# SCH_For_IN12.net
KiCad netlist of a schematic drawn in Altium Designer
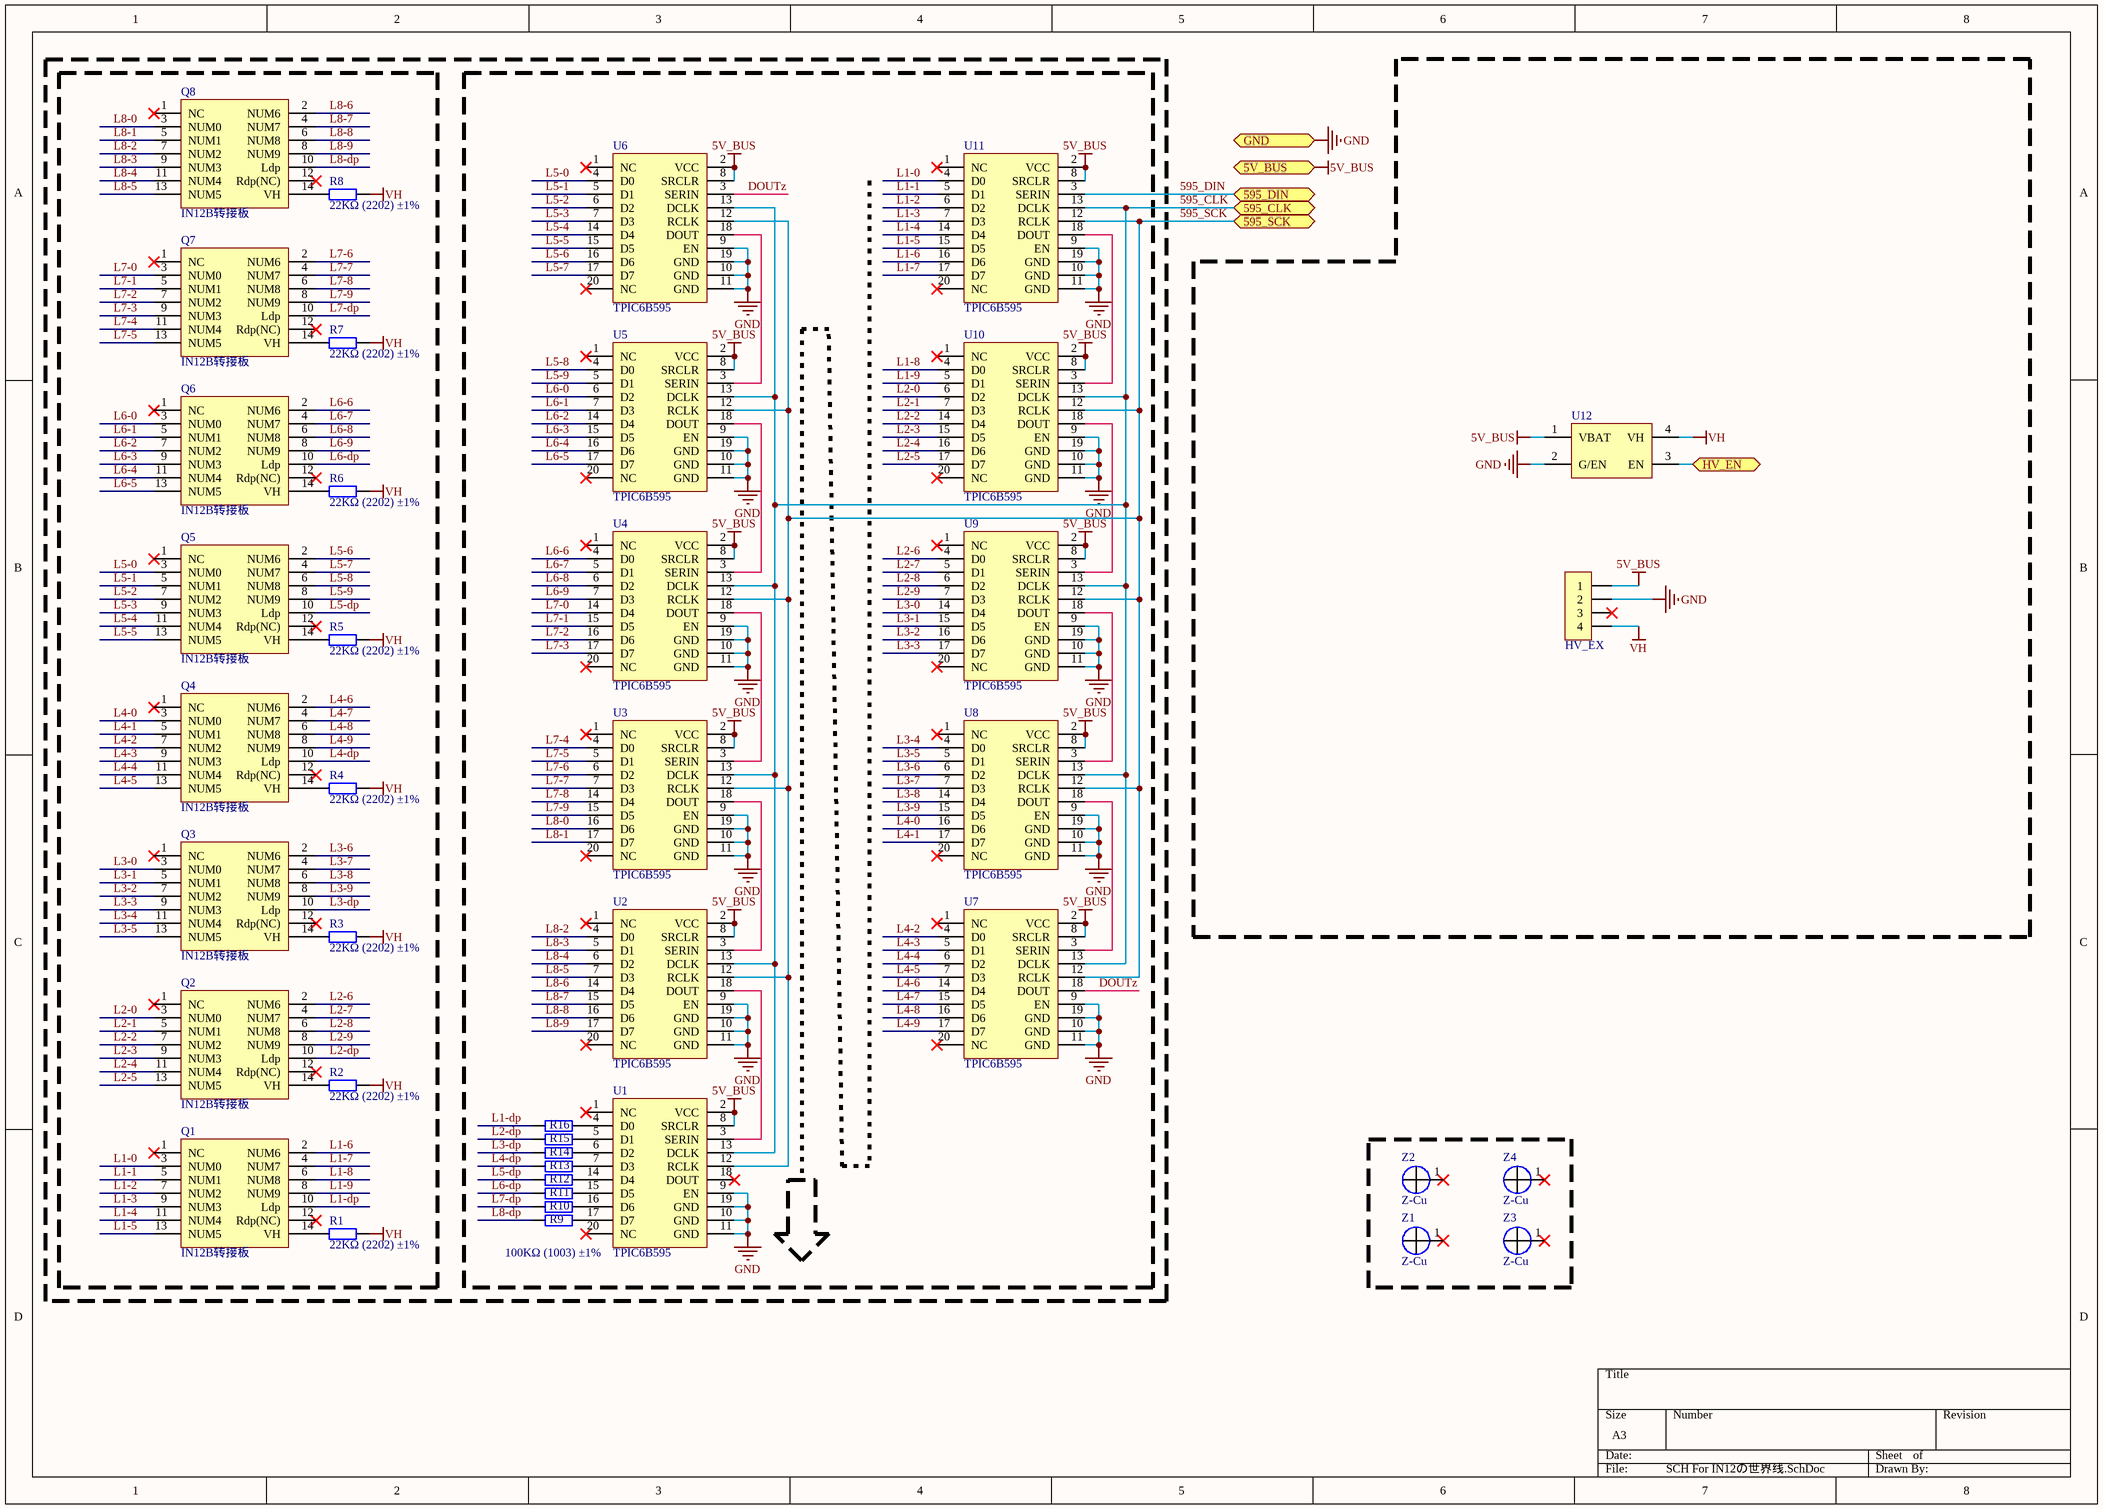
[diagram p0: SCH For IN12の世界线.SchDoc]

(export (version "E")
  (design (tool "Eeschema 10.0.6"))
  (components
    (comp (ref "HV_EX")
      (value "HDR-1X4")
      (footprint "HDR2.54-WS-4P")
      (description "4P接插件")
      (fields (field (name "版权归属") "源创客"))
      (libsource (lib "4.5   - 接插件-脚距2.54") (part "Header 4"))
    )
    (comp (ref "Q1")
      (value "IN12B转接板")
      (footprint "NIXIE IN12 Trans")
      (description "CCCP IN12B转接板")
      (fields (field (name "DESIGN BY：") "simonire@qq.com"))
      (libsource (lib "NIXIE TUBE") (part "NIXIE IN-12B转接板"))
    )
    (comp (ref "Q2")
      (value "IN12B转接板")
      (footprint "NIXIE IN12 Trans")
      (description "CCCP IN12B转接板")
      (fields (field (name "DESIGN BY：") "simonire@qq.com"))
      (libsource (lib "NIXIE TUBE") (part "NIXIE IN-12B转接板"))
    )
    (comp (ref "Q3")
      (value "IN12B转接板")
      (footprint "NIXIE IN12 Trans")
      (description "CCCP IN12B转接板")
      (fields (field (name "DESIGN BY：") "simonire@qq.com"))
      (libsource (lib "NIXIE TUBE") (part "NIXIE IN-12B转接板"))
    )
    (comp (ref "Q4")
      (value "IN12B转接板")
      (footprint "NIXIE IN12 Trans")
      (description "CCCP IN12B转接板")
      (fields (field (name "DESIGN BY：") "simonire@qq.com"))
      (libsource (lib "NIXIE TUBE") (part "NIXIE IN-12B转接板"))
    )
    (comp (ref "Q5")
      (value "IN12B转接板")
      (footprint "NIXIE IN12 Trans")
      (description "CCCP IN12B转接板")
      (fields (field (name "DESIGN BY：") "simonire@qq.com"))
      (libsource (lib "NIXIE TUBE") (part "NIXIE IN-12B转接板"))
    )
    (comp (ref "Q6")
      (value "IN12B转接板")
      (footprint "NIXIE IN12 Trans")
      (description "CCCP IN12B转接板")
      (fields (field (name "DESIGN BY：") "simonire@qq.com"))
      (libsource (lib "NIXIE TUBE") (part "NIXIE IN-12B转接板"))
    )
    (comp (ref "Q7")
      (value "IN12B转接板")
      (footprint "NIXIE IN12 Trans")
      (description "CCCP IN12B转接板")
      (fields (field (name "DESIGN BY：") "simonire@qq.com"))
      (libsource (lib "NIXIE TUBE") (part "NIXIE IN-12B转接板"))
    )
    (comp (ref "Q8")
      (value "IN12B转接板")
      (footprint "NIXIE IN12 Trans")
      (description "CCCP IN12B转接板")
      (fields (field (name "DESIGN BY：") "simonire@qq.com"))
      (libsource (lib "NIXIE TUBE") (part "NIXIE IN-12B转接板"))
    )
    (comp (ref "R1")
      (value "22KΩ (2202) ±1%")
      (footprint "LC-0805_R")
      (description "贴片电阻")
      (libsource (lib "Miscellaneous Devices LC") (part "0805 22KΩ (2202) 1%"))
    )
    (comp (ref "R2")
      (value "22KΩ (2202) ±1%")
      (footprint "LC-0805_R")
      (description "贴片电阻")
      (libsource (lib "Miscellaneous Devices LC") (part "0805 22KΩ (2202) 1%"))
    )
    (comp (ref "R3")
      (value "22KΩ (2202) ±1%")
      (footprint "LC-0805_R")
      (description "贴片电阻")
      (libsource (lib "Miscellaneous Devices LC") (part "0805 22KΩ (2202) 1%"))
    )
    (comp (ref "R4")
      (value "22KΩ (2202) ±1%")
      (footprint "LC-0805_R")
      (description "贴片电阻")
      (libsource (lib "Miscellaneous Devices LC") (part "0805 22KΩ (2202) 1%"))
    )
    (comp (ref "R5")
      (value "22KΩ (2202) ±1%")
      (footprint "LC-0805_R")
      (description "贴片电阻")
      (libsource (lib "Miscellaneous Devices LC") (part "0805 22KΩ (2202) 1%"))
    )
    (comp (ref "R6")
      (value "22KΩ (2202) ±1%")
      (footprint "LC-0805_R")
      (description "贴片电阻")
      (libsource (lib "Miscellaneous Devices LC") (part "0805 22KΩ (2202) 1%"))
    )
    (comp (ref "R7")
      (value "22KΩ (2202) ±1%")
      (footprint "LC-0805_R")
      (description "贴片电阻")
      (libsource (lib "Miscellaneous Devices LC") (part "0805 22KΩ (2202) 1%"))
    )
    (comp (ref "R8")
      (value "22KΩ (2202) ±1%")
      (footprint "LC-0805_R")
      (description "贴片电阻")
      (libsource (lib "Miscellaneous Devices LC") (part "0805 22KΩ (2202) 1%"))
    )
    (comp (ref "R9")
      (value "100KΩ (1003) ±1%")
      (footprint "LC-0603_R")
      (description "贴片电阻")
      (libsource (lib "Miscellaneous Devices LC") (part "0603 100KΩ (1003) 1%"))
    )
    (comp (ref "R10")
      (value "100KΩ (1003) ±1%")
      (footprint "LC-0603_R")
      (description "贴片电阻")
      (libsource (lib "Miscellaneous Devices LC") (part "0603 100KΩ (1003) 1%"))
    )
    (comp (ref "R11")
      (value "100KΩ (1003) ±1%")
      (footprint "LC-0603_R")
      (description "贴片电阻")
      (libsource (lib "Miscellaneous Devices LC") (part "0603 100KΩ (1003) 1%"))
    )
    (comp (ref "R12")
      (value "100KΩ (1003) ±1%")
      (footprint "LC-0603_R")
      (description "贴片电阻")
      (libsource (lib "Miscellaneous Devices LC") (part "0603 100KΩ (1003) 1%"))
    )
    (comp (ref "R13")
      (value "100KΩ (1003) ±1%")
      (footprint "LC-0603_R")
      (description "贴片电阻")
      (libsource (lib "Miscellaneous Devices LC") (part "0603 100KΩ (1003) 1%"))
    )
    (comp (ref "R14")
      (value "100KΩ (1003) ±1%")
      (footprint "LC-0603_R")
      (description "贴片电阻")
      (libsource (lib "Miscellaneous Devices LC") (part "0603 100KΩ (1003) 1%"))
    )
    (comp (ref "R15")
      (value "100KΩ (1003) ±1%")
      (footprint "LC-0603_R")
      (description "贴片电阻")
      (libsource (lib "Miscellaneous Devices LC") (part "0603 100KΩ (1003) 1%"))
    )
    (comp (ref "R16")
      (value "100KΩ (1003) ±1%")
      (footprint "LC-0603_R")
      (description "贴片电阻")
      (libsource (lib "Miscellaneous Devices LC") (part "0603 100KΩ (1003) 1%"))
    )
    (comp (ref "U1")
      (value "TPIC6B595")
      (footprint "SOIC_20W")
      (description "8bits译码驱动器")
      (libsource (lib "NIXIE TUBE") (part "TPIC6B595"))
    )
    (comp (ref "U2")
      (value "TPIC6B595")
      (footprint "SOIC_20W")
      (description "8bits译码驱动器")
      (libsource (lib "NIXIE TUBE") (part "TPIC6B595"))
    )
    (comp (ref "U3")
      (value "TPIC6B595")
      (footprint "SOIC_20W")
      (description "8bits译码驱动器")
      (libsource (lib "NIXIE TUBE") (part "TPIC6B595"))
    )
    (comp (ref "U4")
      (value "TPIC6B595")
      (footprint "SOIC_20W")
      (description "8bits译码驱动器")
      (libsource (lib "NIXIE TUBE") (part "TPIC6B595"))
    )
    (comp (ref "U5")
      (value "TPIC6B595")
      (footprint "SOIC_20W")
      (description "8bits译码驱动器")
      (libsource (lib "NIXIE TUBE") (part "TPIC6B595"))
    )
    (comp (ref "U6")
      (value "TPIC6B595")
      (footprint "SOIC_20W")
      (description "8bits译码驱动器")
      (libsource (lib "NIXIE TUBE") (part "TPIC6B595"))
    )
    (comp (ref "U7")
      (value "TPIC6B595")
      (footprint "SOIC_20W")
      (description "8bits译码驱动器")
      (libsource (lib "NIXIE TUBE") (part "TPIC6B595"))
    )
    (comp (ref "U8")
      (value "TPIC6B595")
      (footprint "SOIC_20W")
      (description "8bits译码驱动器")
      (libsource (lib "NIXIE TUBE") (part "TPIC6B595"))
    )
    (comp (ref "U9")
      (value "TPIC6B595")
      (footprint "SOIC_20W")
      (description "8bits译码驱动器")
      (libsource (lib "NIXIE TUBE") (part "TPIC6B595"))
    )
    (comp (ref "U10")
      (value "TPIC6B595")
      (footprint "SOIC_20W")
      (description "8bits译码驱动器")
      (libsource (lib "NIXIE TUBE") (part "TPIC6B595"))
    )
    (comp (ref "U11")
      (value "TPIC6B595")
      (footprint "SOIC_20W")
      (description "8bits译码驱动器")
      (libsource (lib "NIXIE TUBE") (part "TPIC6B595"))
    )
    (comp (ref "U12")
      (value "DCDC")
      (footprint "VH-DuDu")
      (description "5V升压驱动")
      (fields (field (name "DESIGN BY：") "simonire@qq.com"))
      (libsource (lib "NIXIE TUBE") (part "5V-{gt}VH"))
    )
    (comp (ref "Z1")
      (value "Z-Cu")
      (footprint "M3x5_L")
      (description "Cu")
      (libsource (lib "AD三维集成库") (part "Z-Cu"))
    )
    (comp (ref "Z2")
      (value "Z-Cu")
      (footprint "M3x5_L")
      (description "Cu")
      (libsource (lib "AD三维集成库") (part "Z-Cu"))
    )
    (comp (ref "Z3")
      (value "Z-Cu")
      (footprint "M3x5_L")
      (description "Cu")
      (libsource (lib "AD三维集成库") (part "Z-Cu"))
    )
    (comp (ref "Z4")
      (value "Z-Cu")
      (footprint "M3x5_L")
      (description "Cu")
      (libsource (lib "AD三维集成库") (part "Z-Cu"))
    )
  )
  (nets
    (net (code "1") (name "/595_CLK") (class "Default")
      (node (ref "U1") (pin "13") (pinfunction "DCLK_13") (pintype "passive"))
      (node (ref "U10") (pin "13") (pinfunction "DCLK_13") (pintype "passive"))
      (node (ref "U11") (pin "13") (pinfunction "DCLK_13") (pintype "passive"))
      (node (ref "U2") (pin "13") (pinfunction "DCLK_13") (pintype "passive"))
      (node (ref "U3") (pin "13") (pinfunction "DCLK_13") (pintype "passive"))
      (node (ref "U4") (pin "13") (pinfunction "DCLK_13") (pintype "passive"))
      (node (ref "U5") (pin "13") (pinfunction "DCLK_13") (pintype "passive"))
      (node (ref "U6") (pin "13") (pinfunction "DCLK_13") (pintype "passive"))
      (node (ref "U7") (pin "13") (pinfunction "DCLK_13") (pintype "passive"))
      (node (ref "U8") (pin "13") (pinfunction "DCLK_13") (pintype "passive"))
      (node (ref "U9") (pin "13") (pinfunction "DCLK_13") (pintype "passive"))
    )
    (net (code "2") (name "/595_DIN") (class "Default")
      (node (ref "U11") (pin "3") (pinfunction "SERIN_3") (pintype "passive"))
    )
    (net (code "3") (name "/595_SCK") (class "Default")
      (node (ref "U1") (pin "12") (pinfunction "RCLK_12") (pintype "passive"))
      (node (ref "U10") (pin "12") (pinfunction "RCLK_12") (pintype "passive"))
      (node (ref "U11") (pin "12") (pinfunction "RCLK_12") (pintype "passive"))
      (node (ref "U2") (pin "12") (pinfunction "RCLK_12") (pintype "passive"))
      (node (ref "U3") (pin "12") (pinfunction "RCLK_12") (pintype "passive"))
      (node (ref "U4") (pin "12") (pinfunction "RCLK_12") (pintype "passive"))
      (node (ref "U5") (pin "12") (pinfunction "RCLK_12") (pintype "passive"))
      (node (ref "U6") (pin "12") (pinfunction "RCLK_12") (pintype "passive"))
      (node (ref "U7") (pin "12") (pinfunction "RCLK_12") (pintype "passive"))
      (node (ref "U8") (pin "12") (pinfunction "RCLK_12") (pintype "passive"))
      (node (ref "U9") (pin "12") (pinfunction "RCLK_12") (pintype "passive"))
    )
    (net (code "4") (name "/DOUTz") (class "Default")
      (node (ref "U6") (pin "3") (pinfunction "SERIN_3") (pintype "passive"))
      (node (ref "U7") (pin "18") (pinfunction "DOUT_18") (pintype "passive"))
    )
    (net (code "5") (name "/HV_EN") (class "Default")
      (node (ref "U12") (pin "3") (pinfunction "EN_3") (pintype "passive"))
    )
    (net (code "6") (name "/L1-0") (class "Default")
      (node (ref "Q1") (pin "3") (pinfunction "NUM0_3") (pintype "passive"))
      (node (ref "U11") (pin "4") (pinfunction "D0_4") (pintype "passive"))
    )
    (net (code "7") (name "/L1-1") (class "Default")
      (node (ref "Q1") (pin "5") (pinfunction "NUM1_5") (pintype "passive"))
      (node (ref "U11") (pin "5") (pinfunction "D1_5") (pintype "passive"))
    )
    (net (code "8") (name "/L1-2") (class "Default")
      (node (ref "Q1") (pin "7") (pinfunction "NUM2_7") (pintype "passive"))
      (node (ref "U11") (pin "6") (pinfunction "D2_6") (pintype "passive"))
    )
    (net (code "9") (name "/L1-3") (class "Default")
      (node (ref "Q1") (pin "9") (pinfunction "NUM3_9") (pintype "passive"))
      (node (ref "U11") (pin "7") (pinfunction "D3_7") (pintype "passive"))
    )
    (net (code "10") (name "/L1-4") (class "Default")
      (node (ref "Q1") (pin "11") (pinfunction "NUM4_11") (pintype "passive"))
      (node (ref "U11") (pin "14") (pinfunction "D4_14") (pintype "passive"))
    )
    (net (code "11") (name "/L1-5") (class "Default")
      (node (ref "Q1") (pin "13") (pinfunction "NUM5_13") (pintype "passive"))
      (node (ref "U11") (pin "15") (pinfunction "D5_15") (pintype "passive"))
    )
    (net (code "12") (name "/L1-6") (class "Default")
      (node (ref "Q1") (pin "2") (pinfunction "NUM6_2") (pintype "passive"))
      (node (ref "U11") (pin "16") (pinfunction "D6_16") (pintype "passive"))
    )
    (net (code "13") (name "/L1-7") (class "Default")
      (node (ref "Q1") (pin "4") (pinfunction "NUM7_4") (pintype "passive"))
      (node (ref "U11") (pin "17") (pinfunction "D7_17") (pintype "passive"))
    )
    (net (code "14") (name "/L1-8") (class "Default")
      (node (ref "Q1") (pin "6") (pinfunction "NUM8_6") (pintype "passive"))
      (node (ref "U10") (pin "4") (pinfunction "D0_4") (pintype "passive"))
    )
    (net (code "15") (name "/L1-9") (class "Default")
      (node (ref "Q1") (pin "8") (pinfunction "NUM9_8") (pintype "passive"))
      (node (ref "U10") (pin "5") (pinfunction "D1_5") (pintype "passive"))
    )
    (net (code "16") (name "/L1-dp") (class "Default")
      (node (ref "Q1") (pin "10") (pinfunction "Ldp_10") (pintype "passive"))
      (node (ref "R16") (pin "1") (pinfunction "1_1") (pintype "passive"))
    )
    (net (code "17") (name "/L2-0") (class "Default")
      (node (ref "Q2") (pin "3") (pinfunction "NUM0_3") (pintype "passive"))
      (node (ref "U10") (pin "6") (pinfunction "D2_6") (pintype "passive"))
    )
    (net (code "18") (name "/L2-1") (class "Default")
      (node (ref "Q2") (pin "5") (pinfunction "NUM1_5") (pintype "passive"))
      (node (ref "U10") (pin "7") (pinfunction "D3_7") (pintype "passive"))
    )
    (net (code "19") (name "/L2-2") (class "Default")
      (node (ref "Q2") (pin "7") (pinfunction "NUM2_7") (pintype "passive"))
      (node (ref "U10") (pin "14") (pinfunction "D4_14") (pintype "passive"))
    )
    (net (code "20") (name "/L2-3") (class "Default")
      (node (ref "Q2") (pin "9") (pinfunction "NUM3_9") (pintype "passive"))
      (node (ref "U10") (pin "15") (pinfunction "D5_15") (pintype "passive"))
    )
    (net (code "21") (name "/L2-4") (class "Default")
      (node (ref "Q2") (pin "11") (pinfunction "NUM4_11") (pintype "passive"))
      (node (ref "U10") (pin "16") (pinfunction "D6_16") (pintype "passive"))
    )
    (net (code "22") (name "/L2-5") (class "Default")
      (node (ref "Q2") (pin "13") (pinfunction "NUM5_13") (pintype "passive"))
      (node (ref "U10") (pin "17") (pinfunction "D7_17") (pintype "passive"))
    )
    (net (code "23") (name "/L2-6") (class "Default")
      (node (ref "Q2") (pin "2") (pinfunction "NUM6_2") (pintype "passive"))
      (node (ref "U9") (pin "4") (pinfunction "D0_4") (pintype "passive"))
    )
    (net (code "24") (name "/L2-7") (class "Default")
      (node (ref "Q2") (pin "4") (pinfunction "NUM7_4") (pintype "passive"))
      (node (ref "U9") (pin "5") (pinfunction "D1_5") (pintype "passive"))
    )
    (net (code "25") (name "/L2-8") (class "Default")
      (node (ref "Q2") (pin "6") (pinfunction "NUM8_6") (pintype "passive"))
      (node (ref "U9") (pin "6") (pinfunction "D2_6") (pintype "passive"))
    )
    (net (code "26") (name "/L2-9") (class "Default")
      (node (ref "Q2") (pin "8") (pinfunction "NUM9_8") (pintype "passive"))
      (node (ref "U9") (pin "7") (pinfunction "D3_7") (pintype "passive"))
    )
    (net (code "27") (name "/L2-dp") (class "Default")
      (node (ref "Q2") (pin "10") (pinfunction "Ldp_10") (pintype "passive"))
      (node (ref "R15") (pin "1") (pinfunction "1_1") (pintype "passive"))
    )
    (net (code "28") (name "/L3-0") (class "Default")
      (node (ref "Q3") (pin "3") (pinfunction "NUM0_3") (pintype "passive"))
      (node (ref "U9") (pin "14") (pinfunction "D4_14") (pintype "passive"))
    )
    (net (code "29") (name "/L3-1") (class "Default")
      (node (ref "Q3") (pin "5") (pinfunction "NUM1_5") (pintype "passive"))
      (node (ref "U9") (pin "15") (pinfunction "D5_15") (pintype "passive"))
    )
    (net (code "30") (name "/L3-2") (class "Default")
      (node (ref "Q3") (pin "7") (pinfunction "NUM2_7") (pintype "passive"))
      (node (ref "U9") (pin "16") (pinfunction "D6_16") (pintype "passive"))
    )
    (net (code "31") (name "/L3-3") (class "Default")
      (node (ref "Q3") (pin "9") (pinfunction "NUM3_9") (pintype "passive"))
      (node (ref "U9") (pin "17") (pinfunction "D7_17") (pintype "passive"))
    )
    (net (code "32") (name "/L3-4") (class "Default")
      (node (ref "Q3") (pin "11") (pinfunction "NUM4_11") (pintype "passive"))
      (node (ref "U8") (pin "4") (pinfunction "D0_4") (pintype "passive"))
    )
    (net (code "33") (name "/L3-5") (class "Default")
      (node (ref "Q3") (pin "13") (pinfunction "NUM5_13") (pintype "passive"))
      (node (ref "U8") (pin "5") (pinfunction "D1_5") (pintype "passive"))
    )
    (net (code "34") (name "/L3-6") (class "Default")
      (node (ref "Q3") (pin "2") (pinfunction "NUM6_2") (pintype "passive"))
      (node (ref "U8") (pin "6") (pinfunction "D2_6") (pintype "passive"))
    )
    (net (code "35") (name "/L3-7") (class "Default")
      (node (ref "Q3") (pin "4") (pinfunction "NUM7_4") (pintype "passive"))
      (node (ref "U8") (pin "7") (pinfunction "D3_7") (pintype "passive"))
    )
    (net (code "36") (name "/L3-8") (class "Default")
      (node (ref "Q3") (pin "6") (pinfunction "NUM8_6") (pintype "passive"))
      (node (ref "U8") (pin "14") (pinfunction "D4_14") (pintype "passive"))
    )
    (net (code "37") (name "/L3-9") (class "Default")
      (node (ref "Q3") (pin "8") (pinfunction "NUM9_8") (pintype "passive"))
      (node (ref "U8") (pin "15") (pinfunction "D5_15") (pintype "passive"))
    )
    (net (code "38") (name "/L3-dp") (class "Default")
      (node (ref "Q3") (pin "10") (pinfunction "Ldp_10") (pintype "passive"))
      (node (ref "R14") (pin "1") (pinfunction "1_1") (pintype "passive"))
    )
    (net (code "39") (name "/L4-0") (class "Default")
      (node (ref "Q4") (pin "3") (pinfunction "NUM0_3") (pintype "passive"))
      (node (ref "U8") (pin "16") (pinfunction "D6_16") (pintype "passive"))
    )
    (net (code "40") (name "/L4-1") (class "Default")
      (node (ref "Q4") (pin "5") (pinfunction "NUM1_5") (pintype "passive"))
      (node (ref "U8") (pin "17") (pinfunction "D7_17") (pintype "passive"))
    )
    (net (code "41") (name "/L4-2") (class "Default")
      (node (ref "Q4") (pin "7") (pinfunction "NUM2_7") (pintype "passive"))
      (node (ref "U7") (pin "4") (pinfunction "D0_4") (pintype "passive"))
    )
    (net (code "42") (name "/L4-3") (class "Default")
      (node (ref "Q4") (pin "9") (pinfunction "NUM3_9") (pintype "passive"))
      (node (ref "U7") (pin "5") (pinfunction "D1_5") (pintype "passive"))
    )
    (net (code "43") (name "/L4-4") (class "Default")
      (node (ref "Q4") (pin "11") (pinfunction "NUM4_11") (pintype "passive"))
      (node (ref "U7") (pin "6") (pinfunction "D2_6") (pintype "passive"))
    )
    (net (code "44") (name "/L4-5") (class "Default")
      (node (ref "Q4") (pin "13") (pinfunction "NUM5_13") (pintype "passive"))
      (node (ref "U7") (pin "7") (pinfunction "D3_7") (pintype "passive"))
    )
    (net (code "45") (name "/L4-6") (class "Default")
      (node (ref "Q4") (pin "2") (pinfunction "NUM6_2") (pintype "passive"))
      (node (ref "U7") (pin "14") (pinfunction "D4_14") (pintype "passive"))
    )
    (net (code "46") (name "/L4-7") (class "Default")
      (node (ref "Q4") (pin "4") (pinfunction "NUM7_4") (pintype "passive"))
      (node (ref "U7") (pin "15") (pinfunction "D5_15") (pintype "passive"))
    )
    (net (code "47") (name "/L4-8") (class "Default")
      (node (ref "Q4") (pin "6") (pinfunction "NUM8_6") (pintype "passive"))
      (node (ref "U7") (pin "16") (pinfunction "D6_16") (pintype "passive"))
    )
    (net (code "48") (name "/L4-9") (class "Default")
      (node (ref "Q4") (pin "8") (pinfunction "NUM9_8") (pintype "passive"))
      (node (ref "U7") (pin "17") (pinfunction "D7_17") (pintype "passive"))
    )
    (net (code "49") (name "/L4-dp") (class "Default")
      (node (ref "Q4") (pin "10") (pinfunction "Ldp_10") (pintype "passive"))
      (node (ref "R13") (pin "1") (pinfunction "1_1") (pintype "passive"))
    )
    (net (code "50") (name "/L5-0") (class "Default")
      (node (ref "Q5") (pin "3") (pinfunction "NUM0_3") (pintype "passive"))
      (node (ref "U6") (pin "4") (pinfunction "D0_4") (pintype "passive"))
    )
    (net (code "51") (name "/L5-1") (class "Default")
      (node (ref "Q5") (pin "5") (pinfunction "NUM1_5") (pintype "passive"))
      (node (ref "U6") (pin "5") (pinfunction "D1_5") (pintype "passive"))
    )
    (net (code "52") (name "/L5-2") (class "Default")
      (node (ref "Q5") (pin "7") (pinfunction "NUM2_7") (pintype "passive"))
      (node (ref "U6") (pin "6") (pinfunction "D2_6") (pintype "passive"))
    )
    (net (code "53") (name "/L5-3") (class "Default")
      (node (ref "Q5") (pin "9") (pinfunction "NUM3_9") (pintype "passive"))
      (node (ref "U6") (pin "7") (pinfunction "D3_7") (pintype "passive"))
    )
    (net (code "54") (name "/L5-4") (class "Default")
      (node (ref "Q5") (pin "11") (pinfunction "NUM4_11") (pintype "passive"))
      (node (ref "U6") (pin "14") (pinfunction "D4_14") (pintype "passive"))
    )
    (net (code "55") (name "/L5-5") (class "Default")
      (node (ref "Q5") (pin "13") (pinfunction "NUM5_13") (pintype "passive"))
      (node (ref "U6") (pin "15") (pinfunction "D5_15") (pintype "passive"))
    )
    (net (code "56") (name "/L5-6") (class "Default")
      (node (ref "Q5") (pin "2") (pinfunction "NUM6_2") (pintype "passive"))
      (node (ref "U6") (pin "16") (pinfunction "D6_16") (pintype "passive"))
    )
    (net (code "57") (name "/L5-7") (class "Default")
      (node (ref "Q5") (pin "4") (pinfunction "NUM7_4") (pintype "passive"))
      (node (ref "U6") (pin "17") (pinfunction "D7_17") (pintype "passive"))
    )
    (net (code "58") (name "/L5-8") (class "Default")
      (node (ref "Q5") (pin "6") (pinfunction "NUM8_6") (pintype "passive"))
      (node (ref "U5") (pin "4") (pinfunction "D0_4") (pintype "passive"))
    )
    (net (code "59") (name "/L5-9") (class "Default")
      (node (ref "Q5") (pin "8") (pinfunction "NUM9_8") (pintype "passive"))
      (node (ref "U5") (pin "5") (pinfunction "D1_5") (pintype "passive"))
    )
    (net (code "60") (name "/L5-dp") (class "Default")
      (node (ref "Q5") (pin "10") (pinfunction "Ldp_10") (pintype "passive"))
      (node (ref "R12") (pin "1") (pinfunction "1_1") (pintype "passive"))
    )
    (net (code "61") (name "/L6-0") (class "Default")
      (node (ref "Q6") (pin "3") (pinfunction "NUM0_3") (pintype "passive"))
      (node (ref "U5") (pin "6") (pinfunction "D2_6") (pintype "passive"))
    )
    (net (code "62") (name "/L6-1") (class "Default")
      (node (ref "Q6") (pin "5") (pinfunction "NUM1_5") (pintype "passive"))
      (node (ref "U5") (pin "7") (pinfunction "D3_7") (pintype "passive"))
    )
    (net (code "63") (name "/L6-2") (class "Default")
      (node (ref "Q6") (pin "7") (pinfunction "NUM2_7") (pintype "passive"))
      (node (ref "U5") (pin "14") (pinfunction "D4_14") (pintype "passive"))
    )
    (net (code "64") (name "/L6-3") (class "Default")
      (node (ref "Q6") (pin "9") (pinfunction "NUM3_9") (pintype "passive"))
      (node (ref "U5") (pin "15") (pinfunction "D5_15") (pintype "passive"))
    )
    (net (code "65") (name "/L6-4") (class "Default")
      (node (ref "Q6") (pin "11") (pinfunction "NUM4_11") (pintype "passive"))
      (node (ref "U5") (pin "16") (pinfunction "D6_16") (pintype "passive"))
    )
    (net (code "66") (name "/L6-5") (class "Default")
      (node (ref "Q6") (pin "13") (pinfunction "NUM5_13") (pintype "passive"))
      (node (ref "U5") (pin "17") (pinfunction "D7_17") (pintype "passive"))
    )
    (net (code "67") (name "/L6-6") (class "Default")
      (node (ref "Q6") (pin "2") (pinfunction "NUM6_2") (pintype "passive"))
      (node (ref "U4") (pin "4") (pinfunction "D0_4") (pintype "passive"))
    )
    (net (code "68") (name "/L6-7") (class "Default")
      (node (ref "Q6") (pin "4") (pinfunction "NUM7_4") (pintype "passive"))
      (node (ref "U4") (pin "5") (pinfunction "D1_5") (pintype "passive"))
    )
    (net (code "69") (name "/L6-8") (class "Default")
      (node (ref "Q6") (pin "6") (pinfunction "NUM8_6") (pintype "passive"))
      (node (ref "U4") (pin "6") (pinfunction "D2_6") (pintype "passive"))
    )
    (net (code "70") (name "/L6-9") (class "Default")
      (node (ref "Q6") (pin "8") (pinfunction "NUM9_8") (pintype "passive"))
      (node (ref "U4") (pin "7") (pinfunction "D3_7") (pintype "passive"))
    )
    (net (code "71") (name "/L6-dp") (class "Default")
      (node (ref "Q6") (pin "10") (pinfunction "Ldp_10") (pintype "passive"))
      (node (ref "R11") (pin "1") (pinfunction "1_1") (pintype "passive"))
    )
    (net (code "72") (name "/L7-0") (class "Default")
      (node (ref "Q7") (pin "3") (pinfunction "NUM0_3") (pintype "passive"))
      (node (ref "U4") (pin "14") (pinfunction "D4_14") (pintype "passive"))
    )
    (net (code "73") (name "/L7-1") (class "Default")
      (node (ref "Q7") (pin "5") (pinfunction "NUM1_5") (pintype "passive"))
      (node (ref "U4") (pin "15") (pinfunction "D5_15") (pintype "passive"))
    )
    (net (code "74") (name "/L7-2") (class "Default")
      (node (ref "Q7") (pin "7") (pinfunction "NUM2_7") (pintype "passive"))
      (node (ref "U4") (pin "16") (pinfunction "D6_16") (pintype "passive"))
    )
    (net (code "75") (name "/L7-3") (class "Default")
      (node (ref "Q7") (pin "9") (pinfunction "NUM3_9") (pintype "passive"))
      (node (ref "U4") (pin "17") (pinfunction "D7_17") (pintype "passive"))
    )
    (net (code "76") (name "/L7-4") (class "Default")
      (node (ref "Q7") (pin "11") (pinfunction "NUM4_11") (pintype "passive"))
      (node (ref "U3") (pin "4") (pinfunction "D0_4") (pintype "passive"))
    )
    (net (code "77") (name "/L7-5") (class "Default")
      (node (ref "Q7") (pin "13") (pinfunction "NUM5_13") (pintype "passive"))
      (node (ref "U3") (pin "5") (pinfunction "D1_5") (pintype "passive"))
    )
    (net (code "78") (name "/L7-6") (class "Default")
      (node (ref "Q7") (pin "2") (pinfunction "NUM6_2") (pintype "passive"))
      (node (ref "U3") (pin "6") (pinfunction "D2_6") (pintype "passive"))
    )
    (net (code "79") (name "/L7-7") (class "Default")
      (node (ref "Q7") (pin "4") (pinfunction "NUM7_4") (pintype "passive"))
      (node (ref "U3") (pin "7") (pinfunction "D3_7") (pintype "passive"))
    )
    (net (code "80") (name "/L7-8") (class "Default")
      (node (ref "Q7") (pin "6") (pinfunction "NUM8_6") (pintype "passive"))
      (node (ref "U3") (pin "14") (pinfunction "D4_14") (pintype "passive"))
    )
    (net (code "81") (name "/L7-9") (class "Default")
      (node (ref "Q7") (pin "8") (pinfunction "NUM9_8") (pintype "passive"))
      (node (ref "U3") (pin "15") (pinfunction "D5_15") (pintype "passive"))
    )
    (net (code "82") (name "/L7-dp") (class "Default")
      (node (ref "Q7") (pin "10") (pinfunction "Ldp_10") (pintype "passive"))
      (node (ref "R10") (pin "1") (pinfunction "1_1") (pintype "passive"))
    )
    (net (code "83") (name "/L8-0") (class "Default")
      (node (ref "Q8") (pin "3") (pinfunction "NUM0_3") (pintype "passive"))
      (node (ref "U3") (pin "16") (pinfunction "D6_16") (pintype "passive"))
    )
    (net (code "84") (name "/L8-1") (class "Default")
      (node (ref "Q8") (pin "5") (pinfunction "NUM1_5") (pintype "passive"))
      (node (ref "U3") (pin "17") (pinfunction "D7_17") (pintype "passive"))
    )
    (net (code "85") (name "/L8-2") (class "Default")
      (node (ref "Q8") (pin "7") (pinfunction "NUM2_7") (pintype "passive"))
      (node (ref "U2") (pin "4") (pinfunction "D0_4") (pintype "passive"))
    )
    (net (code "86") (name "/L8-3") (class "Default")
      (node (ref "Q8") (pin "9") (pinfunction "NUM3_9") (pintype "passive"))
      (node (ref "U2") (pin "5") (pinfunction "D1_5") (pintype "passive"))
    )
    (net (code "87") (name "/L8-4") (class "Default")
      (node (ref "Q8") (pin "11") (pinfunction "NUM4_11") (pintype "passive"))
      (node (ref "U2") (pin "6") (pinfunction "D2_6") (pintype "passive"))
    )
    (net (code "88") (name "/L8-5") (class "Default")
      (node (ref "Q8") (pin "13") (pinfunction "NUM5_13") (pintype "passive"))
      (node (ref "U2") (pin "7") (pinfunction "D3_7") (pintype "passive"))
    )
    (net (code "89") (name "/L8-6") (class "Default")
      (node (ref "Q8") (pin "2") (pinfunction "NUM6_2") (pintype "passive"))
      (node (ref "U2") (pin "14") (pinfunction "D4_14") (pintype "passive"))
    )
    (net (code "90") (name "/L8-7") (class "Default")
      (node (ref "Q8") (pin "4") (pinfunction "NUM7_4") (pintype "passive"))
      (node (ref "U2") (pin "15") (pinfunction "D5_15") (pintype "passive"))
    )
    (net (code "91") (name "/L8-8") (class "Default")
      (node (ref "Q8") (pin "6") (pinfunction "NUM8_6") (pintype "passive"))
      (node (ref "U2") (pin "16") (pinfunction "D6_16") (pintype "passive"))
    )
    (net (code "92") (name "/L8-9") (class "Default")
      (node (ref "Q8") (pin "8") (pinfunction "NUM9_8") (pintype "passive"))
      (node (ref "U2") (pin "17") (pinfunction "D7_17") (pintype "passive"))
    )
    (net (code "93") (name "/L8-dp") (class "Default")
      (node (ref "Q8") (pin "10") (pinfunction "Ldp_10") (pintype "passive"))
      (node (ref "R9") (pin "1") (pinfunction "1_1") (pintype "passive"))
    )
    (net (code "94") (name "5V_BUS") (class "Default")
      (node (ref "HV_EX") (pin "1") (pinfunction "1_1") (pintype "passive"))
      (node (ref "U1") (pin "2") (pinfunction "VCC_2") (pintype "passive"))
      (node (ref "U1") (pin "8") (pinfunction "SRCLR_8") (pintype "passive"))
      (node (ref "U10") (pin "2") (pinfunction "VCC_2") (pintype "passive"))
      (node (ref "U10") (pin "8") (pinfunction "SRCLR_8") (pintype "passive"))
      (node (ref "U11") (pin "2") (pinfunction "VCC_2") (pintype "passive"))
      (node (ref "U11") (pin "8") (pinfunction "SRCLR_8") (pintype "passive"))
      (node (ref "U12") (pin "1") (pinfunction "VBAT_1") (pintype "passive"))
      (node (ref "U2") (pin "2") (pinfunction "VCC_2") (pintype "passive"))
      (node (ref "U2") (pin "8") (pinfunction "SRCLR_8") (pintype "passive"))
      (node (ref "U3") (pin "2") (pinfunction "VCC_2") (pintype "passive"))
      (node (ref "U3") (pin "8") (pinfunction "SRCLR_8") (pintype "passive"))
      (node (ref "U4") (pin "2") (pinfunction "VCC_2") (pintype "passive"))
      (node (ref "U4") (pin "8") (pinfunction "SRCLR_8") (pintype "passive"))
      (node (ref "U5") (pin "2") (pinfunction "VCC_2") (pintype "passive"))
      (node (ref "U5") (pin "8") (pinfunction "SRCLR_8") (pintype "passive"))
      (node (ref "U6") (pin "2") (pinfunction "VCC_2") (pintype "passive"))
      (node (ref "U6") (pin "8") (pinfunction "SRCLR_8") (pintype "passive"))
      (node (ref "U7") (pin "2") (pinfunction "VCC_2") (pintype "passive"))
      (node (ref "U7") (pin "8") (pinfunction "SRCLR_8") (pintype "passive"))
      (node (ref "U8") (pin "2") (pinfunction "VCC_2") (pintype "passive"))
      (node (ref "U8") (pin "8") (pinfunction "SRCLR_8") (pintype "passive"))
      (node (ref "U9") (pin "2") (pinfunction "VCC_2") (pintype "passive"))
      (node (ref "U9") (pin "8") (pinfunction "SRCLR_8") (pintype "passive"))
    )
    (net (code "95") (name "GND") (class "Default")
      (node (ref "HV_EX") (pin "2") (pinfunction "2_2") (pintype "passive"))
      (node (ref "U1") (pin "10") (pinfunction "GND_10") (pintype "passive"))
      (node (ref "U1") (pin "11") (pinfunction "GND_11") (pintype "passive"))
      (node (ref "U1") (pin "19") (pinfunction "GND_19") (pintype "passive"))
      (node (ref "U1") (pin "9") (pinfunction "EN_9") (pintype "passive"))
      (node (ref "U10") (pin "10") (pinfunction "GND_10") (pintype "passive"))
      (node (ref "U10") (pin "11") (pinfunction "GND_11") (pintype "passive"))
      (node (ref "U10") (pin "19") (pinfunction "GND_19") (pintype "passive"))
      (node (ref "U10") (pin "9") (pinfunction "EN_9") (pintype "passive"))
      (node (ref "U11") (pin "10") (pinfunction "GND_10") (pintype "passive"))
      (node (ref "U11") (pin "11") (pinfunction "GND_11") (pintype "passive"))
      (node (ref "U11") (pin "19") (pinfunction "GND_19") (pintype "passive"))
      (node (ref "U11") (pin "9") (pinfunction "EN_9") (pintype "passive"))
      (node (ref "U12") (pin "2") (pinfunction "G/EN_2") (pintype "passive"))
      (node (ref "U2") (pin "10") (pinfunction "GND_10") (pintype "passive"))
      (node (ref "U2") (pin "11") (pinfunction "GND_11") (pintype "passive"))
      (node (ref "U2") (pin "19") (pinfunction "GND_19") (pintype "passive"))
      (node (ref "U2") (pin "9") (pinfunction "EN_9") (pintype "passive"))
      (node (ref "U3") (pin "10") (pinfunction "GND_10") (pintype "passive"))
      (node (ref "U3") (pin "11") (pinfunction "GND_11") (pintype "passive"))
      (node (ref "U3") (pin "19") (pinfunction "GND_19") (pintype "passive"))
      (node (ref "U3") (pin "9") (pinfunction "EN_9") (pintype "passive"))
      (node (ref "U4") (pin "10") (pinfunction "GND_10") (pintype "passive"))
      (node (ref "U4") (pin "11") (pinfunction "GND_11") (pintype "passive"))
      (node (ref "U4") (pin "19") (pinfunction "GND_19") (pintype "passive"))
      (node (ref "U4") (pin "9") (pinfunction "EN_9") (pintype "passive"))
      (node (ref "U5") (pin "10") (pinfunction "GND_10") (pintype "passive"))
      (node (ref "U5") (pin "11") (pinfunction "GND_11") (pintype "passive"))
      (node (ref "U5") (pin "19") (pinfunction "GND_19") (pintype "passive"))
      (node (ref "U5") (pin "9") (pinfunction "EN_9") (pintype "passive"))
      (node (ref "U6") (pin "10") (pinfunction "GND_10") (pintype "passive"))
      (node (ref "U6") (pin "11") (pinfunction "GND_11") (pintype "passive"))
      (node (ref "U6") (pin "19") (pinfunction "GND_19") (pintype "passive"))
      (node (ref "U6") (pin "9") (pinfunction "EN_9") (pintype "passive"))
      (node (ref "U7") (pin "10") (pinfunction "GND_10") (pintype "passive"))
      (node (ref "U7") (pin "11") (pinfunction "GND_11") (pintype "passive"))
      (node (ref "U7") (pin "19") (pinfunction "GND_19") (pintype "passive"))
      (node (ref "U7") (pin "9") (pinfunction "EN_9") (pintype "passive"))
      (node (ref "U8") (pin "10") (pinfunction "GND_10") (pintype "passive"))
      (node (ref "U8") (pin "11") (pinfunction "GND_11") (pintype "passive"))
      (node (ref "U8") (pin "19") (pinfunction "GND_19") (pintype "passive"))
      (node (ref "U8") (pin "9") (pinfunction "EN_9") (pintype "passive"))
      (node (ref "U9") (pin "10") (pinfunction "GND_10") (pintype "passive"))
      (node (ref "U9") (pin "11") (pinfunction "GND_11") (pintype "passive"))
      (node (ref "U9") (pin "19") (pinfunction "GND_19") (pintype "passive"))
      (node (ref "U9") (pin "9") (pinfunction "EN_9") (pintype "passive"))
    )
    (net (code "96") (name "Net-(Q1-VH)") (class "Default")
      (node (ref "Q1") (pin "14") (pinfunction "VH_14") (pintype "passive"))
      (node (ref "R1") (pin "1") (pinfunction "1_1") (pintype "passive"))
    )
    (net (code "97") (name "Net-(Q2-VH)") (class "Default")
      (node (ref "Q2") (pin "14") (pinfunction "VH_14") (pintype "passive"))
      (node (ref "R2") (pin "1") (pinfunction "1_1") (pintype "passive"))
    )
    (net (code "98") (name "Net-(Q3-VH)") (class "Default")
      (node (ref "Q3") (pin "14") (pinfunction "VH_14") (pintype "passive"))
      (node (ref "R3") (pin "1") (pinfunction "1_1") (pintype "passive"))
    )
    (net (code "99") (name "Net-(Q4-VH)") (class "Default")
      (node (ref "Q4") (pin "14") (pinfunction "VH_14") (pintype "passive"))
      (node (ref "R4") (pin "1") (pinfunction "1_1") (pintype "passive"))
    )
    (net (code "100") (name "Net-(Q5-VH)") (class "Default")
      (node (ref "Q5") (pin "14") (pinfunction "VH_14") (pintype "passive"))
      (node (ref "R5") (pin "1") (pinfunction "1_1") (pintype "passive"))
    )
    (net (code "101") (name "Net-(Q6-VH)") (class "Default")
      (node (ref "Q6") (pin "14") (pinfunction "VH_14") (pintype "passive"))
      (node (ref "R6") (pin "1") (pinfunction "1_1") (pintype "passive"))
    )
    (net (code "102") (name "Net-(Q7-VH)") (class "Default")
      (node (ref "Q7") (pin "14") (pinfunction "VH_14") (pintype "passive"))
      (node (ref "R7") (pin "1") (pinfunction "1_1") (pintype "passive"))
    )
    (net (code "103") (name "Net-(Q8-VH)") (class "Default")
      (node (ref "Q8") (pin "14") (pinfunction "VH_14") (pintype "passive"))
      (node (ref "R8") (pin "1") (pinfunction "1_1") (pintype "passive"))
    )
    (net (code "104") (name "Net-(U1-D0)") (class "Default")
      (node (ref "R16") (pin "2") (pinfunction "2_2") (pintype "passive"))
      (node (ref "U1") (pin "4") (pinfunction "D0_4") (pintype "passive"))
    )
    (net (code "105") (name "Net-(U1-D1)") (class "Default")
      (node (ref "R15") (pin "2") (pinfunction "2_2") (pintype "passive"))
      (node (ref "U1") (pin "5") (pinfunction "D1_5") (pintype "passive"))
    )
    (net (code "106") (name "Net-(U1-D2)") (class "Default")
      (node (ref "R14") (pin "2") (pinfunction "2_2") (pintype "passive"))
      (node (ref "U1") (pin "6") (pinfunction "D2_6") (pintype "passive"))
    )
    (net (code "107") (name "Net-(U1-D3)") (class "Default")
      (node (ref "R13") (pin "2") (pinfunction "2_2") (pintype "passive"))
      (node (ref "U1") (pin "7") (pinfunction "D3_7") (pintype "passive"))
    )
    (net (code "108") (name "Net-(U1-D4)") (class "Default")
      (node (ref "R12") (pin "2") (pinfunction "2_2") (pintype "passive"))
      (node (ref "U1") (pin "14") (pinfunction "D4_14") (pintype "passive"))
    )
    (net (code "109") (name "Net-(U1-D5)") (class "Default")
      (node (ref "R11") (pin "2") (pinfunction "2_2") (pintype "passive"))
      (node (ref "U1") (pin "15") (pinfunction "D5_15") (pintype "passive"))
    )
    (net (code "110") (name "Net-(U1-D6)") (class "Default")
      (node (ref "R10") (pin "2") (pinfunction "2_2") (pintype "passive"))
      (node (ref "U1") (pin "16") (pinfunction "D6_16") (pintype "passive"))
    )
    (net (code "111") (name "Net-(U1-D7)") (class "Default")
      (node (ref "R9") (pin "2") (pinfunction "2_2") (pintype "passive"))
      (node (ref "U1") (pin "17") (pinfunction "D7_17") (pintype "passive"))
    )
    (net (code "112") (name "Net-(U1-SERIN)") (class "Default")
      (node (ref "U1") (pin "3") (pinfunction "SERIN_3") (pintype "passive"))
      (node (ref "U2") (pin "18") (pinfunction "DOUT_18") (pintype "passive"))
    )
    (net (code "113") (name "Net-(U2-SERIN)") (class "Default")
      (node (ref "U2") (pin "3") (pinfunction "SERIN_3") (pintype "passive"))
      (node (ref "U3") (pin "18") (pinfunction "DOUT_18") (pintype "passive"))
    )
    (net (code "114") (name "Net-(U3-SERIN)") (class "Default")
      (node (ref "U3") (pin "3") (pinfunction "SERIN_3") (pintype "passive"))
      (node (ref "U4") (pin "18") (pinfunction "DOUT_18") (pintype "passive"))
    )
    (net (code "115") (name "Net-(U4-SERIN)") (class "Default")
      (node (ref "U4") (pin "3") (pinfunction "SERIN_3") (pintype "passive"))
      (node (ref "U5") (pin "18") (pinfunction "DOUT_18") (pintype "passive"))
    )
    (net (code "116") (name "Net-(U5-SERIN)") (class "Default")
      (node (ref "U5") (pin "3") (pinfunction "SERIN_3") (pintype "passive"))
      (node (ref "U6") (pin "18") (pinfunction "DOUT_18") (pintype "passive"))
    )
    (net (code "117") (name "Net-(U7-SERIN)") (class "Default")
      (node (ref "U7") (pin "3") (pinfunction "SERIN_3") (pintype "passive"))
      (node (ref "U8") (pin "18") (pinfunction "DOUT_18") (pintype "passive"))
    )
    (net (code "118") (name "Net-(U8-SERIN)") (class "Default")
      (node (ref "U8") (pin "3") (pinfunction "SERIN_3") (pintype "passive"))
      (node (ref "U9") (pin "18") (pinfunction "DOUT_18") (pintype "passive"))
    )
    (net (code "119") (name "Net-(U10-DOUT)") (class "Default")
      (node (ref "U10") (pin "18") (pinfunction "DOUT_18") (pintype "passive"))
      (node (ref "U9") (pin "3") (pinfunction "SERIN_3") (pintype "passive"))
    )
    (net (code "120") (name "Net-(U10-SERIN)") (class "Default")
      (node (ref "U10") (pin "3") (pinfunction "SERIN_3") (pintype "passive"))
      (node (ref "U11") (pin "18") (pinfunction "DOUT_18") (pintype "passive"))
    )
    (net (code "121") (name "VH") (class "Default")
      (node (ref "HV_EX") (pin "4") (pinfunction "4_4") (pintype "passive"))
      (node (ref "R1") (pin "2") (pinfunction "2_2") (pintype "passive"))
      (node (ref "R2") (pin "2") (pinfunction "2_2") (pintype "passive"))
      (node (ref "R3") (pin "2") (pinfunction "2_2") (pintype "passive"))
      (node (ref "R4") (pin "2") (pinfunction "2_2") (pintype "passive"))
      (node (ref "R5") (pin "2") (pinfunction "2_2") (pintype "passive"))
      (node (ref "R6") (pin "2") (pinfunction "2_2") (pintype "passive"))
      (node (ref "R7") (pin "2") (pinfunction "2_2") (pintype "passive"))
      (node (ref "R8") (pin "2") (pinfunction "2_2") (pintype "passive"))
      (node (ref "U12") (pin "4") (pinfunction "VH_4") (pintype "passive"))
    )
    (net (code "122") (name "unconnected-(HV_EX-Pad3)") (class "Default")
      (node (ref "HV_EX") (pin "3") (pinfunction "3_3") (pintype "passive+no_connect"))
    )
    (net (code "123") (name "unconnected-(Q1-NC-Pad1)") (class "Default")
      (node (ref "Q1") (pin "1") (pinfunction "NC_1") (pintype "passive+no_connect"))
    )
    (net (code "124") (name "unconnected-(Q1-Rdp(NC)-Pad12)") (class "Default")
      (node (ref "Q1") (pin "12") (pinfunction "Rdp(NC)_12") (pintype "passive+no_connect"))
    )
    (net (code "125") (name "unconnected-(Q2-NC-Pad1)") (class "Default")
      (node (ref "Q2") (pin "1") (pinfunction "NC_1") (pintype "passive+no_connect"))
    )
    (net (code "126") (name "unconnected-(Q2-Rdp(NC)-Pad12)") (class "Default")
      (node (ref "Q2") (pin "12") (pinfunction "Rdp(NC)_12") (pintype "passive+no_connect"))
    )
    (net (code "127") (name "unconnected-(Q3-NC-Pad1)") (class "Default")
      (node (ref "Q3") (pin "1") (pinfunction "NC_1") (pintype "passive+no_connect"))
    )
    (net (code "128") (name "unconnected-(Q3-Rdp(NC)-Pad12)") (class "Default")
      (node (ref "Q3") (pin "12") (pinfunction "Rdp(NC)_12") (pintype "passive+no_connect"))
    )
    (net (code "129") (name "unconnected-(Q4-NC-Pad1)") (class "Default")
      (node (ref "Q4") (pin "1") (pinfunction "NC_1") (pintype "passive+no_connect"))
    )
    (net (code "130") (name "unconnected-(Q4-Rdp(NC)-Pad12)") (class "Default")
      (node (ref "Q4") (pin "12") (pinfunction "Rdp(NC)_12") (pintype "passive+no_connect"))
    )
    (net (code "131") (name "unconnected-(Q5-NC-Pad1)") (class "Default")
      (node (ref "Q5") (pin "1") (pinfunction "NC_1") (pintype "passive+no_connect"))
    )
    (net (code "132") (name "unconnected-(Q5-Rdp(NC)-Pad12)") (class "Default")
      (node (ref "Q5") (pin "12") (pinfunction "Rdp(NC)_12") (pintype "passive+no_connect"))
    )
    (net (code "133") (name "unconnected-(Q6-NC-Pad1)") (class "Default")
      (node (ref "Q6") (pin "1") (pinfunction "NC_1") (pintype "passive+no_connect"))
    )
    (net (code "134") (name "unconnected-(Q6-Rdp(NC)-Pad12)") (class "Default")
      (node (ref "Q6") (pin "12") (pinfunction "Rdp(NC)_12") (pintype "passive+no_connect"))
    )
    (net (code "135") (name "unconnected-(Q7-NC-Pad1)") (class "Default")
      (node (ref "Q7") (pin "1") (pinfunction "NC_1") (pintype "passive+no_connect"))
    )
    (net (code "136") (name "unconnected-(Q7-Rdp(NC)-Pad12)") (class "Default")
      (node (ref "Q7") (pin "12") (pinfunction "Rdp(NC)_12") (pintype "passive+no_connect"))
    )
    (net (code "137") (name "unconnected-(Q8-NC-Pad1)") (class "Default")
      (node (ref "Q8") (pin "1") (pinfunction "NC_1") (pintype "passive+no_connect"))
    )
    (net (code "138") (name "unconnected-(Q8-Rdp(NC)-Pad12)") (class "Default")
      (node (ref "Q8") (pin "12") (pinfunction "Rdp(NC)_12") (pintype "passive+no_connect"))
    )
    (net (code "139") (name "unconnected-(U1-DOUT-Pad18)") (class "Default")
      (node (ref "U1") (pin "18") (pinfunction "DOUT_18") (pintype "passive+no_connect"))
    )
    (net (code "140") (name "unconnected-(U1-NC-Pad1)") (class "Default")
      (node (ref "U1") (pin "1") (pinfunction "NC_1") (pintype "passive+no_connect"))
    )
    (net (code "141") (name "unconnected-(U1-NC-Pad20)") (class "Default")
      (node (ref "U1") (pin "20") (pinfunction "NC_20") (pintype "passive+no_connect"))
    )
    (net (code "142") (name "unconnected-(U2-NC-Pad1)") (class "Default")
      (node (ref "U2") (pin "1") (pinfunction "NC_1") (pintype "passive+no_connect"))
    )
    (net (code "143") (name "unconnected-(U2-NC-Pad20)") (class "Default")
      (node (ref "U2") (pin "20") (pinfunction "NC_20") (pintype "passive+no_connect"))
    )
    (net (code "144") (name "unconnected-(U3-NC-Pad1)") (class "Default")
      (node (ref "U3") (pin "1") (pinfunction "NC_1") (pintype "passive+no_connect"))
    )
    (net (code "145") (name "unconnected-(U3-NC-Pad20)") (class "Default")
      (node (ref "U3") (pin "20") (pinfunction "NC_20") (pintype "passive+no_connect"))
    )
    (net (code "146") (name "unconnected-(U4-NC-Pad1)") (class "Default")
      (node (ref "U4") (pin "1") (pinfunction "NC_1") (pintype "passive+no_connect"))
    )
    (net (code "147") (name "unconnected-(U4-NC-Pad20)") (class "Default")
      (node (ref "U4") (pin "20") (pinfunction "NC_20") (pintype "passive+no_connect"))
    )
    (net (code "148") (name "unconnected-(U5-NC-Pad1)") (class "Default")
      (node (ref "U5") (pin "1") (pinfunction "NC_1") (pintype "passive+no_connect"))
    )
    (net (code "149") (name "unconnected-(U5-NC-Pad20)") (class "Default")
      (node (ref "U5") (pin "20") (pinfunction "NC_20") (pintype "passive+no_connect"))
    )
    (net (code "150") (name "unconnected-(U6-NC-Pad1)") (class "Default")
      (node (ref "U6") (pin "1") (pinfunction "NC_1") (pintype "passive+no_connect"))
    )
    (net (code "151") (name "unconnected-(U6-NC-Pad20)") (class "Default")
      (node (ref "U6") (pin "20") (pinfunction "NC_20") (pintype "passive+no_connect"))
    )
    (net (code "152") (name "unconnected-(U7-NC-Pad1)") (class "Default")
      (node (ref "U7") (pin "1") (pinfunction "NC_1") (pintype "passive+no_connect"))
    )
    (net (code "153") (name "unconnected-(U7-NC-Pad20)") (class "Default")
      (node (ref "U7") (pin "20") (pinfunction "NC_20") (pintype "passive+no_connect"))
    )
    (net (code "154") (name "unconnected-(U8-NC-Pad1)") (class "Default")
      (node (ref "U8") (pin "1") (pinfunction "NC_1") (pintype "passive+no_connect"))
    )
    (net (code "155") (name "unconnected-(U8-NC-Pad20)") (class "Default")
      (node (ref "U8") (pin "20") (pinfunction "NC_20") (pintype "passive+no_connect"))
    )
    (net (code "156") (name "unconnected-(U9-NC-Pad1)") (class "Default")
      (node (ref "U9") (pin "1") (pinfunction "NC_1") (pintype "passive+no_connect"))
    )
    (net (code "157") (name "unconnected-(U9-NC-Pad20)") (class "Default")
      (node (ref "U9") (pin "20") (pinfunction "NC_20") (pintype "passive+no_connect"))
    )
    (net (code "158") (name "unconnected-(U10-NC-Pad1)") (class "Default")
      (node (ref "U10") (pin "1") (pinfunction "NC_1") (pintype "passive+no_connect"))
    )
    (net (code "159") (name "unconnected-(U10-NC-Pad20)") (class "Default")
      (node (ref "U10") (pin "20") (pinfunction "NC_20") (pintype "passive+no_connect"))
    )
    (net (code "160") (name "unconnected-(U11-NC-Pad1)") (class "Default")
      (node (ref "U11") (pin "1") (pinfunction "NC_1") (pintype "passive+no_connect"))
    )
    (net (code "161") (name "unconnected-(U11-NC-Pad20)") (class "Default")
      (node (ref "U11") (pin "20") (pinfunction "NC_20") (pintype "passive+no_connect"))
    )
    (net (code "162") (name "unconnected-(Z1-Pad1)") (class "Default")
      (node (ref "Z1") (pin "1") (pinfunction "1_1") (pintype "passive+no_connect"))
    )
    (net (code "163") (name "unconnected-(Z2-Pad1)") (class "Default")
      (node (ref "Z2") (pin "1") (pinfunction "1_1") (pintype "passive+no_connect"))
    )
    (net (code "164") (name "unconnected-(Z3-Pad1)") (class "Default")
      (node (ref "Z3") (pin "1") (pinfunction "1_1") (pintype "passive+no_connect"))
    )
    (net (code "165") (name "unconnected-(Z4-Pad1)") (class "Default")
      (node (ref "Z4") (pin "1") (pinfunction "1_1") (pintype "passive+no_connect"))
    )
  )
)
